# 05.net
KiCad netlist of a schematic drawn in Altium Designer
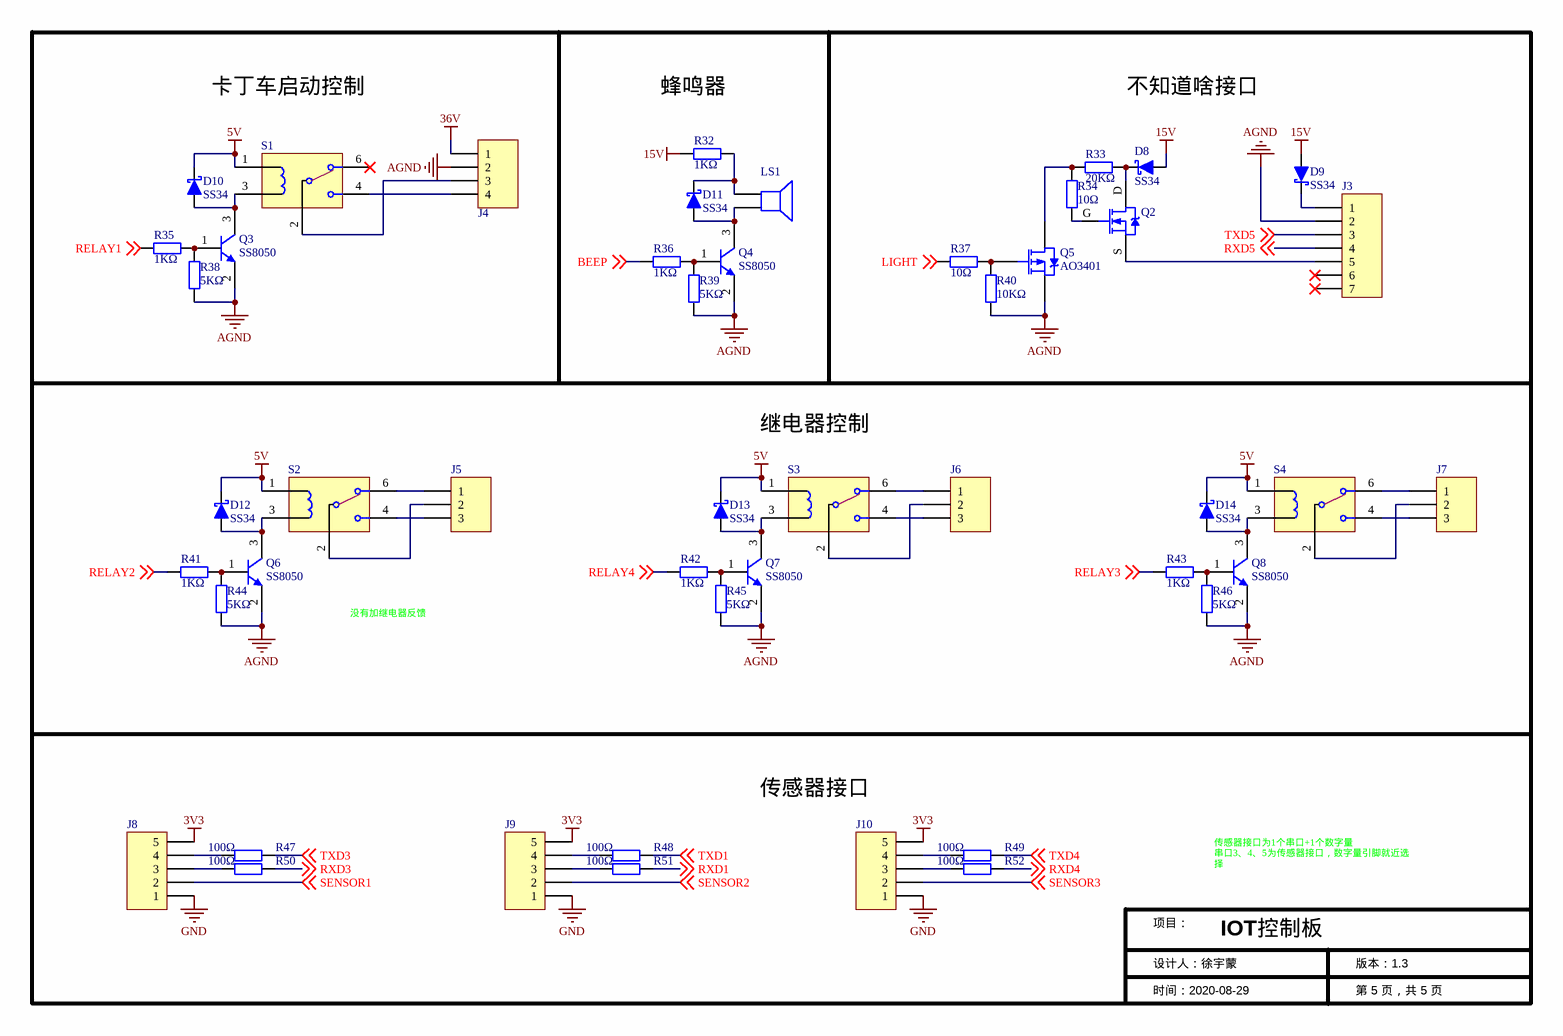
[diagram p0: 05_外部接口与其他部分.SchDoc]

(export (version "E")
  (design (tool "Eeschema 10.0.6"))
  (components
    (comp (ref "D8")
      (value "SS34")
      (footprint "SMA(DO-214AC)")
      (description "Schottky Diode")
      (fields (field (name "PUBLISHER") "Altium Limited"))
      (libsource (lib "元件库") (part "D Schottky"))
    )
    (comp (ref "D9")
      (value "SS34")
      (footprint "SMA(DO-214AC)")
      (description "Schottky Diode")
      (fields (field (name "PUBLISHER") "Altium Limited"))
      (libsource (lib "元件库") (part "D Schottky"))
    )
    (comp (ref "D10")
      (value "SS34")
      (footprint "SMA(DO-214AC)")
      (description "Schottky Diode")
      (fields (field (name "PUBLISHER") "Altium Limited"))
      (libsource (lib "元件库") (part "D Schottky"))
    )
    (comp (ref "D11")
      (value "SS34")
      (footprint "SMA(DO-214AC)")
      (description "Schottky Diode")
      (fields (field (name "PUBLISHER") "Altium Limited"))
      (libsource (lib "元件库") (part "D Schottky"))
    )
    (comp (ref "D12")
      (value "SS34")
      (footprint "SMA(DO-214AC)")
      (description "Schottky Diode")
      (fields (field (name "PUBLISHER") "Altium Limited"))
      (libsource (lib "元件库") (part "D Schottky"))
    )
    (comp (ref "D13")
      (value "SS34")
      (footprint "SMA(DO-214AC)")
      (description "Schottky Diode")
      (fields (field (name "PUBLISHER") "Altium Limited"))
      (libsource (lib "元件库") (part "D Schottky"))
    )
    (comp (ref "D14")
      (value "SS34")
      (footprint "SMA(DO-214AC)")
      (description "Schottky Diode")
      (fields (field (name "PUBLISHER") "Altium Limited"))
      (libsource (lib "元件库") (part "D Schottky"))
    )
    (comp (ref "J3")
      (value "Header7")
      (footprint "Header_7X1_XH_2.54_弯针")
      (description "接插件")
      (libsource (lib "Arrowy_Racing") (part "Header7"))
    )
    (comp (ref "J4")
      (value "Header 4")
      (footprint "Header_4P_XH_2.54_弯脚")
      (description "接插件")
      (fields (field (name "PUBLISHER") "Altium Limited"))
      (libsource (lib "Arrowy_Racing") (part "Header 4"))
    )
    (comp (ref "J5")
      (value "Header3")
      (footprint "Header_3X1_XH_2.54_弯脚")
      (description "接插件")
      (libsource (lib "Arrowy_Racing") (part "Header3"))
    )
    (comp (ref "J6")
      (value "Header3")
      (footprint "Header_3X1_XH_2.54_弯脚")
      (description "接插件")
      (libsource (lib "Arrowy_Racing") (part "Header3"))
    )
    (comp (ref "J7")
      (value "Header3")
      (footprint "Header_3X1_XH_2.54_弯脚")
      (description "接插件")
      (libsource (lib "Arrowy_Racing") (part "Header3"))
    )
    (comp (ref "J8")
      (value "Header5")
      (footprint "Header_5X1_XH_2.54_弯针")
      (description "接插件")
      (libsource (lib "Arrowy_Racing") (part "Header5"))
    )
    (comp (ref "J9")
      (value "Header5")
      (footprint "Header_5X1_XH_2.54_弯针")
      (description "接插件")
      (libsource (lib "Arrowy_Racing") (part "Header5"))
    )
    (comp (ref "J10")
      (value "Header5")
      (footprint "Header_5X1_XH_2.54_弯针")
      (description "接插件")
      (libsource (lib "Arrowy_Racing") (part "Header5"))
    )
    (comp (ref "LS1")
      (value "蜂鸣器")
      (footprint "蜂鸣器 9*5mm")
      (description "Loudspeaker")
      (fields (field (name "PUBLISHER") "Altium Limited"))
      (libsource (lib "Arrowy_Racing") (part "Speaker"))
    )
    (comp (ref "Q2")
      (value "AO3400")
      (footprint "SOT-23-MOSFET")
      (description "N沟道MOS管")
      (libsource (lib "Arrowy_Racing") (part "MOSFET-N"))
    )
    (comp (ref "Q3")
      (value "SS8050")
      (footprint "SOT-23")
      (description "NPN贴片三极管")
      (fields (field (name "PUBLISHER") "Altium Limited"))
      (libsource (lib "Arrowy_Racing") (part "SS8050"))
    )
    (comp (ref "Q4")
      (value "SS8050")
      (footprint "SOT-23")
      (description "NPN贴片三极管")
      (fields (field (name "PUBLISHER") "Altium Limited"))
      (libsource (lib "Arrowy_Racing") (part "SS8050"))
    )
    (comp (ref "Q5")
      (value "AO3401")
      (footprint "SOT-23-MOSFET")
      (description "P沟道MOS管")
      (libsource (lib "Arrowy_Racing") (part "MOSFET-P"))
    )
    (comp (ref "Q6")
      (value "SS8050")
      (footprint "SOT-23")
      (description "NPN贴片三极管")
      (fields (field (name "PUBLISHER") "Altium Limited"))
      (libsource (lib "Arrowy_Racing") (part "SS8050"))
    )
    (comp (ref "Q7")
      (value "SS8050")
      (footprint "SOT-23")
      (description "NPN贴片三极管")
      (fields (field (name "PUBLISHER") "Altium Limited"))
      (libsource (lib "Arrowy_Racing") (part "SS8050"))
    )
    (comp (ref "Q8")
      (value "SS8050")
      (footprint "SOT-23")
      (description "NPN贴片三极管")
      (fields (field (name "PUBLISHER") "Altium Limited"))
      (libsource (lib "Arrowy_Racing") (part "SS8050"))
    )
    (comp (ref "R32")
      (value "1KΩ")
      (footprint "0603")
      (description "贴片电阻")
      (fields (field (name "Comment") "Res") (field (name "PUBLISHER") "Altium Limited"))
      (libsource (lib "") (part "Res_1"))
    )
    (comp (ref "R33")
      (value "20KΩ")
      (footprint "0603")
      (description "贴片电阻")
      (fields (field (name "Comment") "Res") (field (name "PUBLISHER") "Altium Limited"))
      (libsource (lib "") (part "Res_1"))
    )
    (comp (ref "R34")
      (value "10Ω")
      (footprint "0603")
      (description "贴片电阻")
      (fields (field (name "Comment") "Res") (field (name "PUBLISHER") "Altium Limited"))
      (libsource (lib "") (part "Res_3"))
    )
    (comp (ref "R35")
      (value "1KΩ")
      (footprint "0603")
      (description "贴片电阻")
      (fields (field (name "Comment") "Res") (field (name "PUBLISHER") "Altium Limited"))
      (libsource (lib "") (part "Res_1"))
    )
    (comp (ref "R36")
      (value "1KΩ")
      (footprint "0603")
      (description "贴片电阻")
      (fields (field (name "Comment") "Res") (field (name "PUBLISHER") "Altium Limited"))
      (libsource (lib "") (part "Res_1"))
    )
    (comp (ref "R37")
      (value "10Ω")
      (footprint "0603")
      (description "贴片电阻")
      (fields (field (name "Comment") "Res") (field (name "PUBLISHER") "Altium Limited"))
      (libsource (lib "") (part "Res_1"))
    )
    (comp (ref "R38")
      (value "5KΩ")
      (footprint "0603")
      (description "贴片电阻")
      (fields (field (name "Comment") "Res") (field (name "PUBLISHER") "Altium Limited"))
      (libsource (lib "Arrowy_Racing") (part "Res"))
    )
    (comp (ref "R39")
      (value "5KΩ")
      (footprint "0603")
      (description "贴片电阻")
      (fields (field (name "Comment") "Res") (field (name "PUBLISHER") "Altium Limited"))
      (libsource (lib "Arrowy_Racing") (part "Res"))
    )
    (comp (ref "R40")
      (value "10KΩ")
      (footprint "0603")
      (description "贴片电阻")
      (fields (field (name "Comment") "Res") (field (name "PUBLISHER") "Altium Limited"))
      (libsource (lib "Arrowy_Racing") (part "Res"))
    )
    (comp (ref "R41")
      (value "1KΩ")
      (footprint "0603")
      (description "贴片电阻")
      (fields (field (name "Comment") "Res") (field (name "PUBLISHER") "Altium Limited"))
      (libsource (lib "") (part "Res_1"))
    )
    (comp (ref "R42")
      (value "1KΩ")
      (footprint "0603")
      (description "贴片电阻")
      (fields (field (name "Comment") "Res") (field (name "PUBLISHER") "Altium Limited"))
      (libsource (lib "") (part "Res_1"))
    )
    (comp (ref "R43")
      (value "1KΩ")
      (footprint "0603")
      (description "贴片电阻")
      (fields (field (name "Comment") "Res") (field (name "PUBLISHER") "Altium Limited"))
      (libsource (lib "") (part "Res_1"))
    )
    (comp (ref "R44")
      (value "5KΩ")
      (footprint "0603")
      (description "贴片电阻")
      (fields (field (name "Comment") "Res") (field (name "PUBLISHER") "Altium Limited"))
      (libsource (lib "Arrowy_Racing") (part "Res"))
    )
    (comp (ref "R45")
      (value "5KΩ")
      (footprint "0603")
      (description "贴片电阻")
      (fields (field (name "Comment") "Res") (field (name "PUBLISHER") "Altium Limited"))
      (libsource (lib "Arrowy_Racing") (part "Res"))
    )
    (comp (ref "R46")
      (value "5KΩ")
      (footprint "0603")
      (description "贴片电阻")
      (fields (field (name "Comment") "Res") (field (name "PUBLISHER") "Altium Limited"))
      (libsource (lib "Arrowy_Racing") (part "Res"))
    )
    (comp (ref "R47")
      (value "100Ω")
      (footprint "0603")
      (description "贴片电阻")
      (fields (field (name "Comment") "Res") (field (name "PUBLISHER") "Altium Limited"))
      (libsource (lib "") (part "Res_2"))
    )
    (comp (ref "R48")
      (value "100Ω")
      (footprint "0603")
      (description "贴片电阻")
      (fields (field (name "Comment") "Res") (field (name "PUBLISHER") "Altium Limited"))
      (libsource (lib "") (part "Res_2"))
    )
    (comp (ref "R49")
      (value "100Ω")
      (footprint "0603")
      (description "贴片电阻")
      (fields (field (name "Comment") "Res") (field (name "PUBLISHER") "Altium Limited"))
      (libsource (lib "") (part "Res_2"))
    )
    (comp (ref "R50")
      (value "100Ω")
      (footprint "0603")
      (description "贴片电阻")
      (fields (field (name "Comment") "Res") (field (name "PUBLISHER") "Altium Limited"))
      (libsource (lib "") (part "Res_2"))
    )
    (comp (ref "R51")
      (value "100Ω")
      (footprint "0603")
      (description "贴片电阻")
      (fields (field (name "Comment") "Res") (field (name "PUBLISHER") "Altium Limited"))
      (libsource (lib "") (part "Res_2"))
    )
    (comp (ref "R52")
      (value "100Ω")
      (footprint "0603")
      (description "贴片电阻")
      (fields (field (name "Comment") "Res") (field (name "PUBLISHER") "Altium Limited"))
      (libsource (lib "") (part "Res_2"))
    )
    (comp (ref "S1")
      (value "Delay")
      (footprint "SongLe_Relay")
      (description "松乐继电器")
      (libsource (lib "Arrowy_Racing") (part "SongLe_Relay"))
    )
    (comp (ref "S2")
      (value "Delay")
      (footprint "SongLe_Relay")
      (description "松乐继电器")
      (libsource (lib "Arrowy_Racing") (part "SongLe_Relay"))
    )
    (comp (ref "S3")
      (value "Delay")
      (footprint "SongLe_Relay")
      (description "松乐继电器")
      (libsource (lib "Arrowy_Racing") (part "SongLe_Relay"))
    )
    (comp (ref "S4")
      (value "Delay")
      (footprint "SongLe_Relay")
      (description "松乐继电器")
      (libsource (lib "Arrowy_Racing") (part "SongLe_Relay"))
    )
  )
  (nets
    (net (code "1") (name "3V3") (class "Default")
      (node (ref "J10") (pin "5") (pinfunction "5_5") (pintype "passive"))
      (node (ref "J8") (pin "5") (pinfunction "5_5") (pintype "passive"))
      (node (ref "J9") (pin "5") (pinfunction "5_5") (pintype "passive"))
    )
    (net (code "2") (name "5V") (class "Default")
      (node (ref "D10") (pin "2") (pinfunction "K_2") (pintype "passive"))
      (node (ref "D12") (pin "2") (pinfunction "K_2") (pintype "passive"))
      (node (ref "D13") (pin "2") (pinfunction "K_2") (pintype "passive"))
      (node (ref "D14") (pin "2") (pinfunction "K_2") (pintype "passive"))
      (node (ref "S1") (pin "1") (pinfunction "1_1") (pintype "passive"))
      (node (ref "S2") (pin "1") (pinfunction "1_1") (pintype "passive"))
      (node (ref "S3") (pin "1") (pinfunction "1_1") (pintype "passive"))
      (node (ref "S4") (pin "1") (pinfunction "1_1") (pintype "passive"))
    )
    (net (code "3") (name "15V") (class "Default")
      (node (ref "D8") (pin "1") (pinfunction "A_1") (pintype "passive"))
      (node (ref "D9") (pin "1") (pinfunction "A_1") (pintype "passive"))
      (node (ref "R32") (pin "2") (pinfunction "2_2") (pintype "passive"))
    )
    (net (code "4") (name "36V") (class "Default")
      (node (ref "J4") (pin "1") (pinfunction "1_1") (pintype "passive"))
    )
    (net (code "5") (name "AGND") (class "Default")
      (node (ref "J3") (pin "2") (pinfunction "2_2") (pintype "passive"))
      (node (ref "J4") (pin "2") (pinfunction "2_2") (pintype "passive"))
      (node (ref "Q3") (pin "2") (pinfunction "E_2") (pintype "passive"))
      (node (ref "Q4") (pin "2") (pinfunction "E_2") (pintype "passive"))
      (node (ref "Q5") (pin "S") (pinfunction "S_S") (pintype "passive"))
      (node (ref "Q6") (pin "2") (pinfunction "E_2") (pintype "passive"))
      (node (ref "Q7") (pin "2") (pinfunction "E_2") (pintype "passive"))
      (node (ref "Q8") (pin "2") (pinfunction "E_2") (pintype "passive"))
      (node (ref "R38") (pin "1") (pinfunction "1_1") (pintype "passive"))
      (node (ref "R39") (pin "1") (pinfunction "1_1") (pintype "passive"))
      (node (ref "R40") (pin "1") (pinfunction "1_1") (pintype "passive"))
      (node (ref "R44") (pin "1") (pinfunction "1_1") (pintype "passive"))
      (node (ref "R45") (pin "1") (pinfunction "1_1") (pintype "passive"))
      (node (ref "R46") (pin "1") (pinfunction "1_1") (pintype "passive"))
    )
    (net (code "6") (name "BEEP") (class "Default")
      (node (ref "R36") (pin "2") (pinfunction "2_2") (pintype "passive"))
    )
    (net (code "7") (name "GND") (class "Default")
      (node (ref "J10") (pin "1") (pinfunction "1_1") (pintype "passive"))
      (node (ref "J8") (pin "1") (pinfunction "1_1") (pintype "passive"))
      (node (ref "J9") (pin "1") (pinfunction "1_1") (pintype "passive"))
    )
    (net (code "8") (name "LIGHT") (class "Default")
      (node (ref "R37") (pin "2") (pinfunction "2_2") (pintype "passive"))
    )
    (net (code "9") (name "Net-(D8-K)") (class "Default")
      (node (ref "D8") (pin "2") (pinfunction "K_2") (pintype "passive"))
      (node (ref "Q2") (pin "D") (pinfunction "D_D") (pintype "passive"))
      (node (ref "R33") (pin "1") (pinfunction "1_1") (pintype "passive"))
    )
    (net (code "10") (name "Net-(D9-K)") (class "Default")
      (node (ref "D9") (pin "2") (pinfunction "K_2") (pintype "passive"))
      (node (ref "J3") (pin "1") (pinfunction "1_1") (pintype "passive"))
    )
    (net (code "11") (name "Net-(D10-A)") (class "Default")
      (node (ref "D10") (pin "1") (pinfunction "A_1") (pintype "passive"))
      (node (ref "Q3") (pin "3") (pinfunction "C_3") (pintype "passive"))
      (node (ref "S1") (pin "3") (pinfunction "3_3") (pintype "passive"))
    )
    (net (code "12") (name "Net-(D11-A)") (class "Default")
      (node (ref "D11") (pin "1") (pinfunction "A_1") (pintype "passive"))
      (node (ref "LS1") (pin "2") (pinfunction "2_2") (pintype "passive"))
      (node (ref "Q4") (pin "3") (pinfunction "C_3") (pintype "passive"))
    )
    (net (code "13") (name "Net-(D11-K)") (class "Default")
      (node (ref "D11") (pin "2") (pinfunction "K_2") (pintype "passive"))
      (node (ref "LS1") (pin "1") (pinfunction "1_1") (pintype "passive"))
      (node (ref "R32") (pin "1") (pinfunction "1_1") (pintype "passive"))
    )
    (net (code "14") (name "Net-(D12-A)") (class "Default")
      (node (ref "D12") (pin "1") (pinfunction "A_1") (pintype "passive"))
      (node (ref "Q6") (pin "3") (pinfunction "C_3") (pintype "passive"))
      (node (ref "S2") (pin "3") (pinfunction "3_3") (pintype "passive"))
    )
    (net (code "15") (name "Net-(D13-A)") (class "Default")
      (node (ref "D13") (pin "1") (pinfunction "A_1") (pintype "passive"))
      (node (ref "Q7") (pin "3") (pinfunction "C_3") (pintype "passive"))
      (node (ref "S3") (pin "3") (pinfunction "3_3") (pintype "passive"))
    )
    (net (code "16") (name "Net-(D14-A)") (class "Default")
      (node (ref "D14") (pin "1") (pinfunction "A_1") (pintype "passive"))
      (node (ref "Q8") (pin "3") (pinfunction "C_3") (pintype "passive"))
      (node (ref "S4") (pin "3") (pinfunction "3_3") (pintype "passive"))
    )
    (net (code "17") (name "Net-(J3-Pad5)") (class "Default")
      (node (ref "J3") (pin "5") (pinfunction "5_5") (pintype "passive"))
      (node (ref "Q2") (pin "S") (pinfunction "S_S") (pintype "passive"))
    )
    (net (code "18") (name "Net-(J4-Pad3)") (class "Default")
      (node (ref "J4") (pin "3") (pinfunction "3_3") (pintype "passive"))
      (node (ref "S1") (pin "2") (pinfunction "2_2") (pintype "passive"))
    )
    (net (code "19") (name "Net-(J4-Pad4)") (class "Default")
      (node (ref "J4") (pin "4") (pinfunction "4_4") (pintype "passive"))
      (node (ref "S1") (pin "4") (pinfunction "4_4") (pintype "passive"))
    )
    (net (code "20") (name "Net-(J5-Pad1)") (class "Default")
      (node (ref "J5") (pin "1") (pinfunction "1_1") (pintype "passive"))
      (node (ref "S2") (pin "6") (pinfunction "6_6") (pintype "passive"))
    )
    (net (code "21") (name "Net-(J5-Pad2)") (class "Default")
      (node (ref "J5") (pin "2") (pinfunction "2_2") (pintype "passive"))
      (node (ref "S2") (pin "2") (pinfunction "2_2") (pintype "passive"))
    )
    (net (code "22") (name "Net-(J5-Pad3)") (class "Default")
      (node (ref "J5") (pin "3") (pinfunction "3_3") (pintype "passive"))
      (node (ref "S2") (pin "4") (pinfunction "4_4") (pintype "passive"))
    )
    (net (code "23") (name "Net-(J6-Pad1)") (class "Default")
      (node (ref "J6") (pin "1") (pinfunction "1_1") (pintype "passive"))
      (node (ref "S3") (pin "6") (pinfunction "6_6") (pintype "passive"))
    )
    (net (code "24") (name "Net-(J6-Pad2)") (class "Default")
      (node (ref "J6") (pin "2") (pinfunction "2_2") (pintype "passive"))
      (node (ref "S3") (pin "2") (pinfunction "2_2") (pintype "passive"))
    )
    (net (code "25") (name "Net-(J6-Pad3)") (class "Default")
      (node (ref "J6") (pin "3") (pinfunction "3_3") (pintype "passive"))
      (node (ref "S3") (pin "4") (pinfunction "4_4") (pintype "passive"))
    )
    (net (code "26") (name "Net-(J7-Pad1)") (class "Default")
      (node (ref "J7") (pin "1") (pinfunction "1_1") (pintype "passive"))
      (node (ref "S4") (pin "6") (pinfunction "6_6") (pintype "passive"))
    )
    (net (code "27") (name "Net-(J7-Pad2)") (class "Default")
      (node (ref "J7") (pin "2") (pinfunction "2_2") (pintype "passive"))
      (node (ref "S4") (pin "2") (pinfunction "2_2") (pintype "passive"))
    )
    (net (code "28") (name "Net-(J7-Pad3)") (class "Default")
      (node (ref "J7") (pin "3") (pinfunction "3_3") (pintype "passive"))
      (node (ref "S4") (pin "4") (pinfunction "4_4") (pintype "passive"))
    )
    (net (code "29") (name "Net-(J8-Pad3)") (class "Default")
      (node (ref "J8") (pin "3") (pinfunction "3_3") (pintype "passive"))
      (node (ref "R50") (pin "1") (pinfunction "1_1") (pintype "passive"))
    )
    (net (code "30") (name "Net-(J8-Pad4)") (class "Default")
      (node (ref "J8") (pin "4") (pinfunction "4_4") (pintype "passive"))
      (node (ref "R47") (pin "1") (pinfunction "1_1") (pintype "passive"))
    )
    (net (code "31") (name "Net-(J9-Pad3)") (class "Default")
      (node (ref "J9") (pin "3") (pinfunction "3_3") (pintype "passive"))
      (node (ref "R51") (pin "1") (pinfunction "1_1") (pintype "passive"))
    )
    (net (code "32") (name "Net-(J9-Pad4)") (class "Default")
      (node (ref "J9") (pin "4") (pinfunction "4_4") (pintype "passive"))
      (node (ref "R48") (pin "1") (pinfunction "1_1") (pintype "passive"))
    )
    (net (code "33") (name "Net-(J10-Pad3)") (class "Default")
      (node (ref "J10") (pin "3") (pinfunction "3_3") (pintype "passive"))
      (node (ref "R52") (pin "1") (pinfunction "1_1") (pintype "passive"))
    )
    (net (code "34") (name "Net-(J10-Pad4)") (class "Default")
      (node (ref "J10") (pin "4") (pinfunction "4_4") (pintype "passive"))
      (node (ref "R49") (pin "1") (pinfunction "1_1") (pintype "passive"))
    )
    (net (code "35") (name "Net-(Q2-PadG)") (class "Default")
      (node (ref "Q2") (pin "G") (pinfunction "G_G") (pintype "passive"))
      (node (ref "R34") (pin "2") (pinfunction "2_2") (pintype "passive"))
    )
    (net (code "36") (name "Net-(Q3-B)") (class "Default")
      (node (ref "Q3") (pin "1") (pinfunction "B_1") (pintype "passive"))
      (node (ref "R35") (pin "1") (pinfunction "1_1") (pintype "passive"))
      (node (ref "R38") (pin "2") (pinfunction "2_2") (pintype "passive"))
    )
    (net (code "37") (name "Net-(Q4-B)") (class "Default")
      (node (ref "Q4") (pin "1") (pinfunction "B_1") (pintype "passive"))
      (node (ref "R36") (pin "1") (pinfunction "1_1") (pintype "passive"))
      (node (ref "R39") (pin "2") (pinfunction "2_2") (pintype "passive"))
    )
    (net (code "38") (name "Net-(Q5-PadD)") (class "Default")
      (node (ref "Q5") (pin "D") (pinfunction "D_D") (pintype "passive"))
      (node (ref "R33") (pin "2") (pinfunction "2_2") (pintype "passive"))
      (node (ref "R34") (pin "1") (pinfunction "1_1") (pintype "passive"))
    )
    (net (code "39") (name "Net-(Q5-PadG)") (class "Default")
      (node (ref "Q5") (pin "G") (pinfunction "G_G") (pintype "passive"))
      (node (ref "R37") (pin "1") (pinfunction "1_1") (pintype "passive"))
      (node (ref "R40") (pin "2") (pinfunction "2_2") (pintype "passive"))
    )
    (net (code "40") (name "Net-(Q6-B)") (class "Default")
      (node (ref "Q6") (pin "1") (pinfunction "B_1") (pintype "passive"))
      (node (ref "R41") (pin "1") (pinfunction "1_1") (pintype "passive"))
      (node (ref "R44") (pin "2") (pinfunction "2_2") (pintype "passive"))
    )
    (net (code "41") (name "Net-(Q7-B)") (class "Default")
      (node (ref "Q7") (pin "1") (pinfunction "B_1") (pintype "passive"))
      (node (ref "R42") (pin "1") (pinfunction "1_1") (pintype "passive"))
      (node (ref "R45") (pin "2") (pinfunction "2_2") (pintype "passive"))
    )
    (net (code "42") (name "Net-(Q8-B)") (class "Default")
      (node (ref "Q8") (pin "1") (pinfunction "B_1") (pintype "passive"))
      (node (ref "R43") (pin "1") (pinfunction "1_1") (pintype "passive"))
      (node (ref "R46") (pin "2") (pinfunction "2_2") (pintype "passive"))
    )
    (net (code "43") (name "RELAY1") (class "Default")
      (node (ref "R35") (pin "2") (pinfunction "2_2") (pintype "passive"))
    )
    (net (code "44") (name "RELAY2") (class "Default")
      (node (ref "R41") (pin "2") (pinfunction "2_2") (pintype "passive"))
    )
    (net (code "45") (name "RELAY3") (class "Default")
      (node (ref "R43") (pin "2") (pinfunction "2_2") (pintype "passive"))
    )
    (net (code "46") (name "RELAY4") (class "Default")
      (node (ref "R42") (pin "2") (pinfunction "2_2") (pintype "passive"))
    )
    (net (code "47") (name "RXD1") (class "Default")
      (node (ref "R51") (pin "2") (pinfunction "2_2") (pintype "passive"))
    )
    (net (code "48") (name "RXD3") (class "Default")
      (node (ref "R50") (pin "2") (pinfunction "2_2") (pintype "passive"))
    )
    (net (code "49") (name "RXD4") (class "Default")
      (node (ref "R52") (pin "2") (pinfunction "2_2") (pintype "passive"))
    )
    (net (code "50") (name "RXD5") (class "Default")
      (node (ref "J3") (pin "4") (pinfunction "4_4") (pintype "passive"))
    )
    (net (code "51") (name "SENSOR1") (class "Default")
      (node (ref "J8") (pin "2") (pinfunction "2_2") (pintype "passive"))
    )
    (net (code "52") (name "SENSOR2") (class "Default")
      (node (ref "J9") (pin "2") (pinfunction "2_2") (pintype "passive"))
    )
    (net (code "53") (name "SENSOR3") (class "Default")
      (node (ref "J10") (pin "2") (pinfunction "2_2") (pintype "passive"))
    )
    (net (code "54") (name "TXD1") (class "Default")
      (node (ref "R48") (pin "2") (pinfunction "2_2") (pintype "passive"))
    )
    (net (code "55") (name "TXD3") (class "Default")
      (node (ref "R47") (pin "2") (pinfunction "2_2") (pintype "passive"))
    )
    (net (code "56") (name "TXD4") (class "Default")
      (node (ref "R49") (pin "2") (pinfunction "2_2") (pintype "passive"))
    )
    (net (code "57") (name "TXD5") (class "Default")
      (node (ref "J3") (pin "3") (pinfunction "3_3") (pintype "passive"))
    )
    (net (code "58") (name "unconnected-(J3-Pad6)") (class "Default")
      (node (ref "J3") (pin "6") (pinfunction "6_6") (pintype "passive+no_connect"))
    )
    (net (code "59") (name "unconnected-(J3-Pad7)") (class "Default")
      (node (ref "J3") (pin "7") (pinfunction "7_7") (pintype "passive+no_connect"))
    )
    (net (code "60") (name "unconnected-(S1-Pad6)") (class "Default")
      (node (ref "S1") (pin "6") (pinfunction "6_6") (pintype "passive+no_connect"))
    )
  )
)
